# 701_GridPos7.net
KiCad netlist of a schematic drawn in Altium Designer
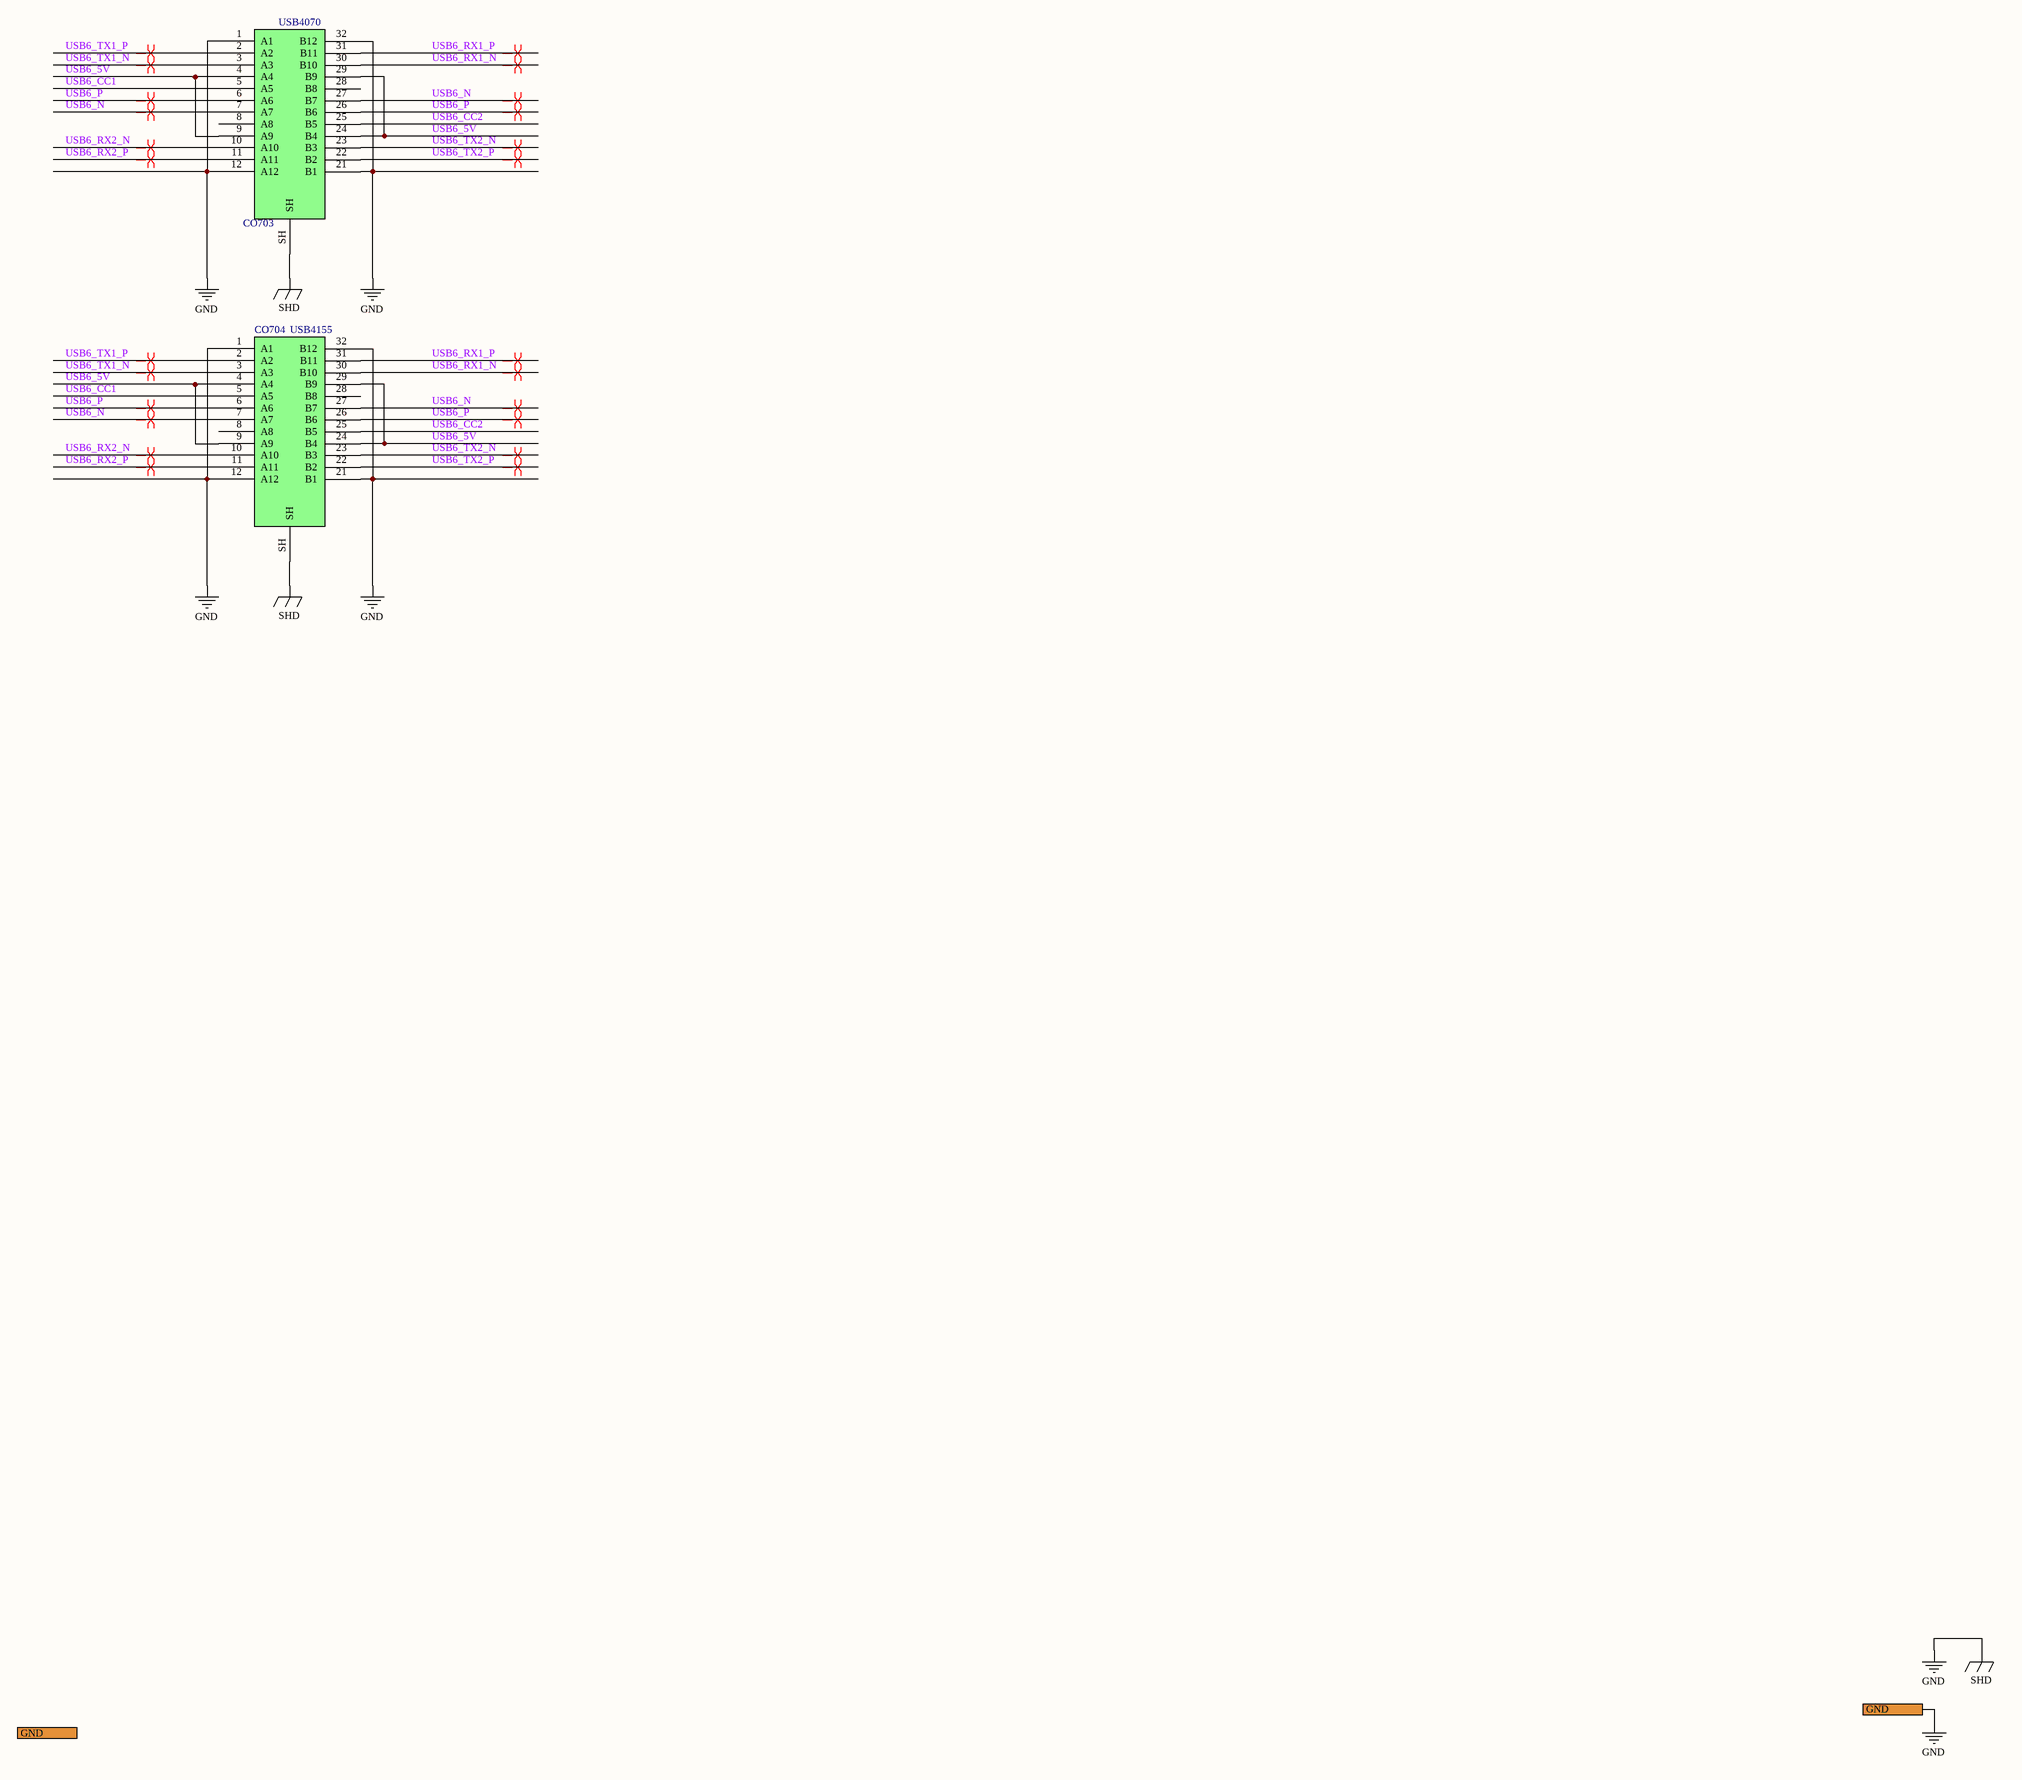
[diagram p0: 701_GridPos7.SchDoc]

(export (version "E")
  (design (tool "Eeschema 10.0.6"))
  (components
    (comp (ref "CO703")
      (value "USB4070")
      (footprint "USB4070-30-C")
      (description "USB C connector Receptacle Vertical")
      (fields
        (field (name "REFVAL") "USB4070")
        (field (name "PART NUMBER") "CO0021")
        (field (name "MANFACTPART") "USB4070-30-C")
      )
      (libsource (lib "GTS_Database") (part "USB-CC"))
    )
    (comp (ref "CO704")
      (value "USB4155")
      (footprint "USB4155-03-C")
      (description "USB C connector Plug Horizontal")
      (fields
        (field (name "REFVAL") "USB4155")
        (field (name "PART NUMBER") "CO0031")
        (field (name "MANFACTPART") "USB4155-03-C")
      )
      (libsource (lib "GTS_Database") (part "USB-CC"))
    )
  )
  (nets
    (net (code "1") (name "/USB6_5V") (class "Default")
      (node (ref "CO703") (pin "24") (pinfunction "B4_24") (pintype "passive"))
      (node (ref "CO703") (pin "29") (pinfunction "B9_29") (pintype "passive"))
      (node (ref "CO703") (pin "4") (pinfunction "A4_4") (pintype "passive"))
      (node (ref "CO703") (pin "9") (pinfunction "A9_9") (pintype "passive"))
      (node (ref "CO704") (pin "24") (pinfunction "B4_24") (pintype "passive"))
      (node (ref "CO704") (pin "29") (pinfunction "B9_29") (pintype "passive"))
      (node (ref "CO704") (pin "4") (pinfunction "A4_4") (pintype "passive"))
      (node (ref "CO704") (pin "9") (pinfunction "A9_9") (pintype "passive"))
    )
    (net (code "2") (name "/USB6_CC1") (class "Default")
      (node (ref "CO703") (pin "5") (pinfunction "A5_5") (pintype "passive"))
      (node (ref "CO704") (pin "5") (pinfunction "A5_5") (pintype "passive"))
    )
    (net (code "3") (name "/USB6_CC2") (class "Default")
      (node (ref "CO703") (pin "25") (pinfunction "B5_25") (pintype "passive"))
      (node (ref "CO704") (pin "25") (pinfunction "B5_25") (pintype "passive"))
    )
    (net (code "4") (name "/USB6_N") (class "Default")
      (node (ref "CO703") (pin "27") (pinfunction "B7_27") (pintype "passive"))
      (node (ref "CO703") (pin "7") (pinfunction "A7_7") (pintype "passive"))
      (node (ref "CO704") (pin "27") (pinfunction "B7_27") (pintype "passive"))
      (node (ref "CO704") (pin "7") (pinfunction "A7_7") (pintype "passive"))
    )
    (net (code "5") (name "/USB6_P") (class "Default")
      (node (ref "CO703") (pin "26") (pinfunction "B6_26") (pintype "passive"))
      (node (ref "CO703") (pin "6") (pinfunction "A6_6") (pintype "passive"))
      (node (ref "CO704") (pin "26") (pinfunction "B6_26") (pintype "passive"))
      (node (ref "CO704") (pin "6") (pinfunction "A6_6") (pintype "passive"))
    )
    (net (code "6") (name "/USB6_RX1_N") (class "Default")
      (node (ref "CO703") (pin "30") (pinfunction "B10_30") (pintype "passive"))
      (node (ref "CO704") (pin "30") (pinfunction "B10_30") (pintype "passive"))
    )
    (net (code "7") (name "/USB6_RX1_P") (class "Default")
      (node (ref "CO703") (pin "31") (pinfunction "B11_31") (pintype "passive"))
      (node (ref "CO704") (pin "31") (pinfunction "B11_31") (pintype "passive"))
    )
    (net (code "8") (name "/USB6_RX2_N") (class "Default")
      (node (ref "CO703") (pin "10") (pinfunction "A10_10") (pintype "passive"))
      (node (ref "CO704") (pin "10") (pinfunction "A10_10") (pintype "passive"))
    )
    (net (code "9") (name "/USB6_RX2_P") (class "Default")
      (node (ref "CO703") (pin "11") (pinfunction "A11_11") (pintype "passive"))
      (node (ref "CO704") (pin "11") (pinfunction "A11_11") (pintype "passive"))
    )
    (net (code "10") (name "/USB6_TX1_N") (class "Default")
      (node (ref "CO703") (pin "3") (pinfunction "A3_3") (pintype "passive"))
      (node (ref "CO704") (pin "3") (pinfunction "A3_3") (pintype "passive"))
    )
    (net (code "11") (name "/USB6_TX1_P") (class "Default")
      (node (ref "CO703") (pin "2") (pinfunction "A2_2") (pintype "passive"))
      (node (ref "CO704") (pin "2") (pinfunction "A2_2") (pintype "passive"))
    )
    (net (code "12") (name "/USB6_TX2_N") (class "Default")
      (node (ref "CO703") (pin "23") (pinfunction "B3_23") (pintype "passive"))
      (node (ref "CO704") (pin "23") (pinfunction "B3_23") (pintype "passive"))
    )
    (net (code "13") (name "/USB6_TX2_P") (class "Default")
      (node (ref "CO703") (pin "22") (pinfunction "B2_22") (pintype "passive"))
      (node (ref "CO704") (pin "22") (pinfunction "B2_22") (pintype "passive"))
    )
    (net (code "14") (name "GND") (class "Default")
      (node (ref "CO703") (pin "1") (pinfunction "A1_1") (pintype "passive"))
      (node (ref "CO703") (pin "12") (pinfunction "A12_12") (pintype "passive"))
      (node (ref "CO703") (pin "21") (pinfunction "B1_21") (pintype "passive"))
      (node (ref "CO703") (pin "32") (pinfunction "B12_32") (pintype "passive"))
      (node (ref "CO703") (pin "SH") (pinfunction "SH_SH") (pintype "power_in"))
      (node (ref "CO704") (pin "1") (pinfunction "A1_1") (pintype "passive"))
      (node (ref "CO704") (pin "12") (pinfunction "A12_12") (pintype "passive"))
      (node (ref "CO704") (pin "21") (pinfunction "B1_21") (pintype "passive"))
      (node (ref "CO704") (pin "32") (pinfunction "B12_32") (pintype "passive"))
      (node (ref "CO704") (pin "SH") (pinfunction "SH_SH") (pintype "power_in"))
    )
    (net (code "15") (name "unconnected-(CO703-A8-Pad8)") (class "Default")
      (node (ref "CO703") (pin "8") (pinfunction "A8_8") (pintype "passive"))
    )
    (net (code "16") (name "unconnected-(CO703-B8-Pad28)") (class "Default")
      (node (ref "CO703") (pin "28") (pinfunction "B8_28") (pintype "passive"))
    )
    (net (code "17") (name "unconnected-(CO704-A8-Pad8)") (class "Default")
      (node (ref "CO704") (pin "8") (pinfunction "A8_8") (pintype "passive"))
    )
    (net (code "18") (name "unconnected-(CO704-B8-Pad28)") (class "Default")
      (node (ref "CO704") (pin "28") (pinfunction "B8_28") (pintype "passive"))
    )
  )
)
